# USB.net
KiCad netlist of a schematic drawn in Altium Designer
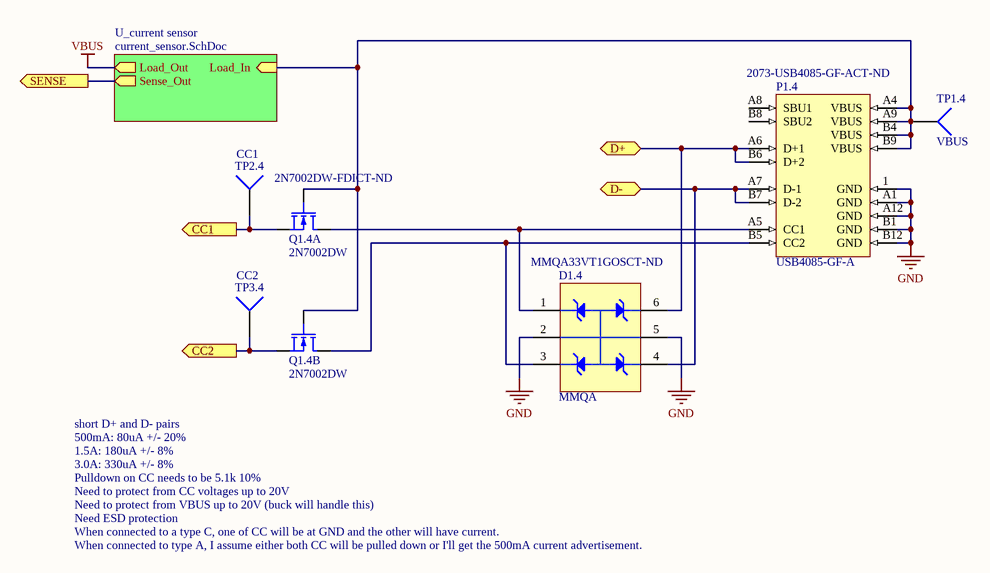
[diagram p0: USB.SchDoc]

(export (version "E")
  (design (tool "Eeschema 10.0.6"))
  (components
    (comp (ref "D1.4")
      (value "MMQA")
      (footprint "SC-74")
      (fields (field (name "SUPPLIER PART NUMBER 1") "MMQA33VT1GOSCT-ND"))
      (libsource (lib "pokey") (part "MMQA"))
    )
    (comp (ref "P1.4")
      (value "USB4085-GF-A")
      (footprint "USB4085-GF-A")
      (description "USB C Connector")
      (fields (field (name "SUPPLIER PART NUMBER 1") "2073-USB4085-GF-ACT-ND"))
      (libsource (lib "pokey") (part "USB4085-GF-A"))
    )
    (comp (ref "Q1.4")
      (value "2N7002DW")
      (footprint "SOT65P210X110-6N")
      (fields (field (name "SUPPLIER PART NUMBER 1") "2N7002DW-FDICT-ND"))
      (libsource (lib "pokey") (part "2N7002DW"))
    )
    (comp (ref "TP1.4")
      (value "VBUS")
      (footprint "Test Point Target 1mm")
      (description "Socket")
      (fields (field (name "PUBLISHER") "Altium Limited"))
      (libsource (lib "Miscellaneous Connectors") (part "Socket"))
    )
    (comp (ref "TP2.4")
      (value "CC1")
      (footprint "Test Point Target 1mm")
      (description "Socket")
      (fields (field (name "PUBLISHER") "Altium Limited"))
      (libsource (lib "Miscellaneous Connectors") (part "Socket"))
    )
    (comp (ref "TP3.4")
      (value "CC2")
      (footprint "Test Point Target 1mm")
      (description "Socket")
      (fields (field (name "PUBLISHER") "Altium Limited"))
      (libsource (lib "Miscellaneous Connectors") (part "Socket"))
    )
  )
  (nets
    (net (code "1") (name "/CC1") (class "Default")
      (node (ref "Q1.4") (pin "4") (pinfunction "S_4") (pintype "passive"))
      (node (ref "TP2.4") (pin "1") (pinfunction "1_1") (pintype "passive"))
    )
    (net (code "2") (name "/CC2") (class "Default")
      (node (ref "Q1.4") (pin "1") (pinfunction "S_1") (pintype "passive"))
      (node (ref "TP3.4") (pin "1") (pinfunction "1_1") (pintype "passive"))
    )
    (net (code "3") (name "/D+") (class "Default")
      (node (ref "D1.4") (pin "6") (pintype "passive"))
      (node (ref "P1.4") (pin "A6") (pinfunction "D+1_A6") (pintype "input"))
      (node (ref "P1.4") (pin "B6") (pinfunction "D+2_B6") (pintype "input"))
    )
    (net (code "4") (name "/D-") (class "Default")
      (node (ref "D1.4") (pin "4") (pintype "passive"))
      (node (ref "P1.4") (pin "A7") (pinfunction "D-1_A7") (pintype "input"))
      (node (ref "P1.4") (pin "B7") (pinfunction "D-2_B7") (pintype "input"))
    )
    (net (code "5") (name "/Load_In") (class "Default")
      (node (ref "P1.4") (pin "A4") (pinfunction "VBUS_A4") (pintype "input"))
      (node (ref "P1.4") (pin "A9") (pinfunction "VBUS_A9") (pintype "input"))
      (node (ref "P1.4") (pin "B4") (pinfunction "VBUS_B4") (pintype "input"))
      (node (ref "P1.4") (pin "B9") (pinfunction "VBUS_B9") (pintype "input"))
      (node (ref "Q1.4") (pin "2") (pinfunction "G_2") (pintype "passive"))
      (node (ref "Q1.4") (pin "5") (pinfunction "G_5") (pintype "passive"))
      (node (ref "TP1.4") (pin "1") (pinfunction "1_1") (pintype "passive"))
    )
    (net (code "7") (name "GND") (class "Default")
      (node (ref "D1.4") (pin "2") (pintype "passive"))
      (node (ref "D1.4") (pin "5") (pintype "passive"))
      (node (ref "P1.4") (pin "1") (pinfunction "GND_1") (pintype "input"))
      (node (ref "P1.4") (pin "A1") (pinfunction "GND_A1") (pintype "input"))
      (node (ref "P1.4") (pin "A12") (pinfunction "GND_A12") (pintype "input"))
      (node (ref "P1.4") (pin "B1") (pinfunction "GND_B1") (pintype "input"))
      (node (ref "P1.4") (pin "B12") (pinfunction "GND_B12") (pintype "input"))
    )
    (net (code "8") (name "Net-(P1.4-CC1)") (class "Default")
      (node (ref "D1.4") (pin "1") (pintype "passive"))
      (node (ref "P1.4") (pin "A5") (pinfunction "CC1_A5") (pintype "input"))
      (node (ref "Q1.4") (pin "3") (pinfunction "D_3") (pintype "passive"))
    )
    (net (code "9") (name "Net-(P1.4-CC2)") (class "Default")
      (node (ref "D1.4") (pin "3") (pintype "passive"))
      (node (ref "P1.4") (pin "B5") (pinfunction "CC2_B5") (pintype "input"))
      (node (ref "Q1.4") (pin "6") (pinfunction "D_6") (pintype "passive"))
    )
    (net (code "11") (name "unconnected-(P1.4-SBU1-PadA8)") (class "Default")
      (node (ref "P1.4") (pin "A8") (pinfunction "SBU1_A8") (pintype "input"))
    )
    (net (code "12") (name "unconnected-(P1.4-SBU2-PadB8)") (class "Default")
      (node (ref "P1.4") (pin "B8") (pinfunction "SBU2_B8") (pintype "input"))
    )
  )
)
